# TrusskeyV2.net
KiCad netlist of a schematic drawn in EAGLE
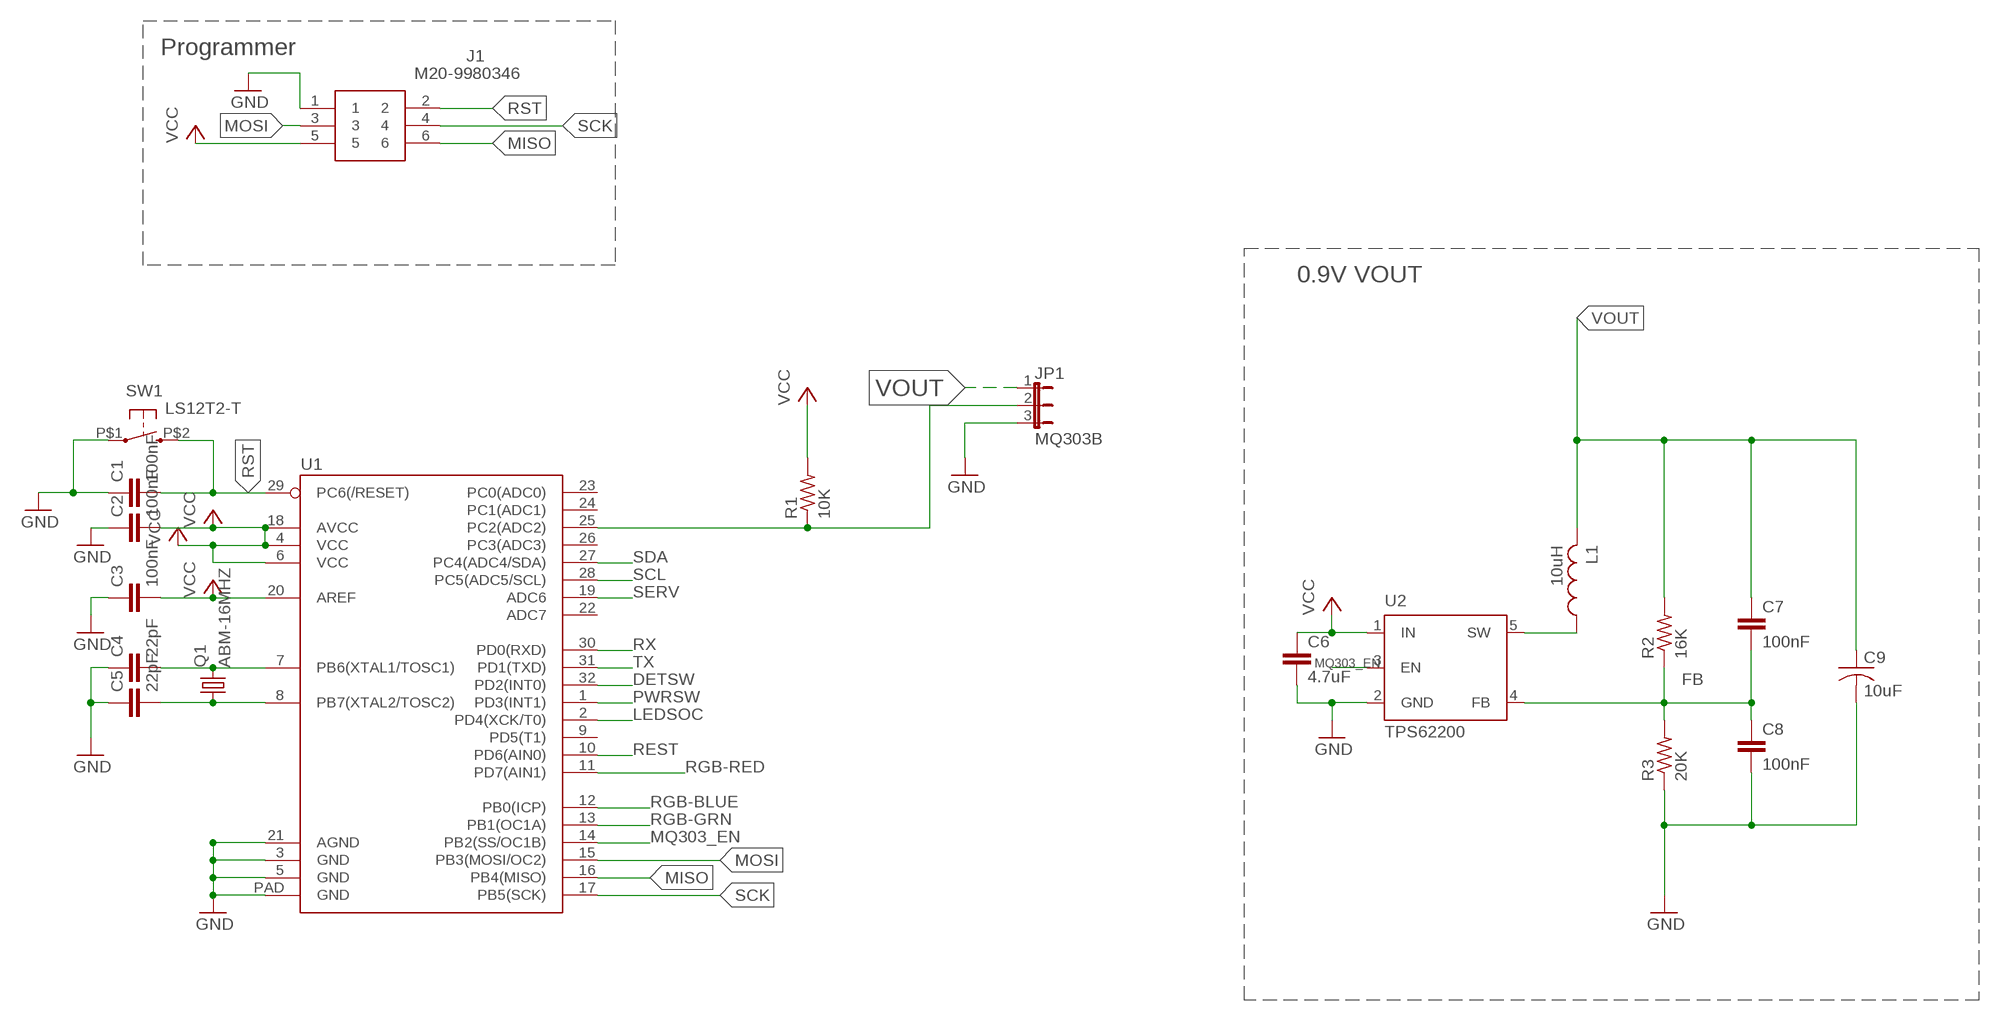
[diagram p0: schematic, sheet 1]
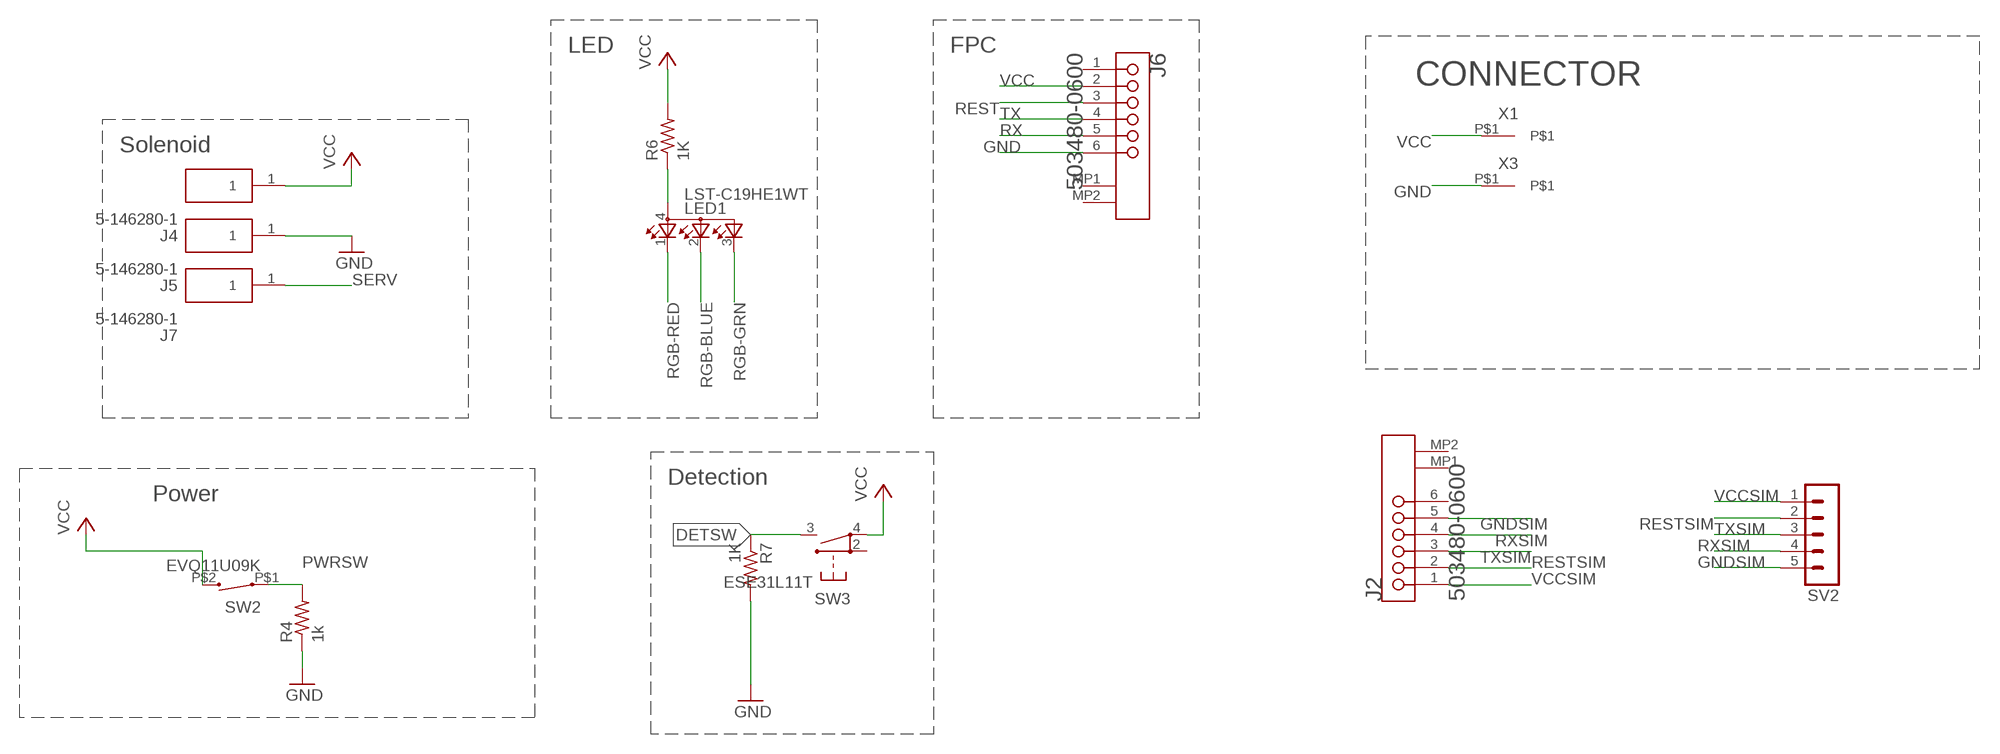
[diagram p1: schematic, sheet 2]
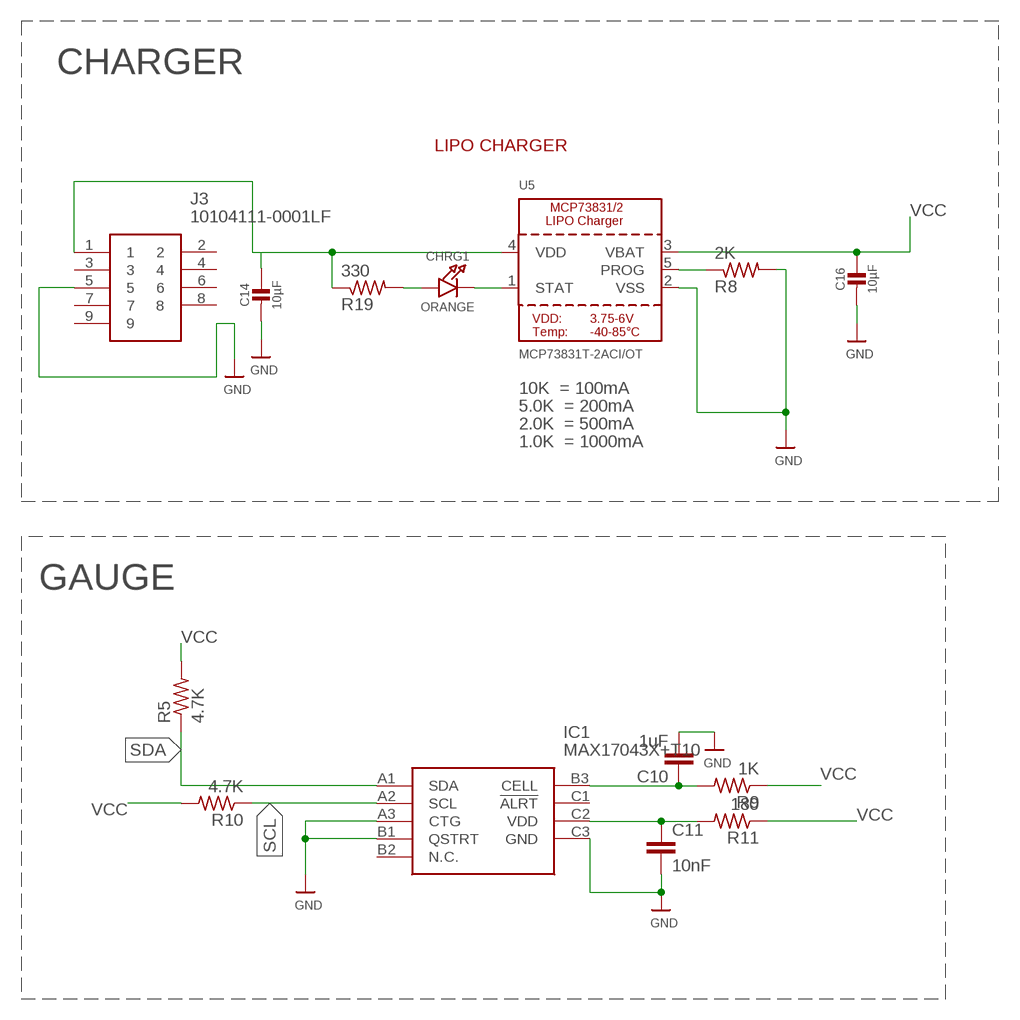
[diagram p2: schematic, sheet 3]

(export (version "E")
  (design (tool "Eeschema 10.0.6"))
  (components
    (comp (ref "J2")
      (value "MOLEX_503480-0600MOLEX_503480-0600_0_0")
      (footprint "eagle-import:MOLEX_503480-0600_0")
      (fields (field (name "MF") "Molex") (field (name "MPN") "503480-0600"))
      (libsource (lib "eagle-import") (part "MOLEX_503480-0600MOLEX_503480-0600_0_0"))
    )
    (comp (ref "J4")
      (value "5-146280-1")
      (footprint "eagle-import:HDRV1W67P0X254_1X1_213X234X821")
      (fields (field (name "MOUSER_PART_NUMBER") "571-51462801"))
      (libsource (lib "eagle-import") (part "5-146280-1"))
    )
    (comp (ref "J5")
      (value "5-146280-1")
      (footprint "eagle-import:HDRV1W67P0X254_1X1_213X234X821")
      (fields (field (name "MOUSER_PART_NUMBER") "571-51462801"))
      (libsource (lib "eagle-import") (part "5-146280-1"))
    )
    (comp (ref "J6")
      (value "MOLEX_503480-0600MOLEX_503480-0600_0_0")
      (footprint "eagle-import:MOLEX_503480-0600_0")
      (fields (field (name "MF") "Molex") (field (name "MPN") "503480-0600"))
      (libsource (lib "eagle-import") (part "MOLEX_503480-0600MOLEX_503480-0600_0_0"))
    )
    (comp (ref "J7")
      (value "5-146280-1")
      (footprint "eagle-import:HDRV1W67P0X254_1X1_213X234X821")
      (fields (field (name "MOUSER_PART_NUMBER") "571-51462801"))
      (libsource (lib "eagle-import") (part "5-146280-1"))
    )
    (comp (ref "LED1")
      (value "LST-C19HE1WT")
      (footprint "eagle-import:LST-C19HE1WT")
      (libsource (lib "eagle-import") (part "LST-C19HE1WT"))
    )
    (comp (ref "R4")
      (value "1k")
      (footprint "eagle-import:R0402")
      (libsource (lib "eagle-import") (part "R-US_R0402"))
    )
    (comp (ref "R6")
      (value "1K")
      (footprint "eagle-import:R0402")
      (libsource (lib "eagle-import") (part "R-US_R0402"))
    )
    (comp (ref "R7")
      (value "1K")
      (footprint "eagle-import:R0402")
      (libsource (lib "eagle-import") (part "R-US_R0402"))
    )
    (comp (ref "SV2")
      (value "MA05-1")
      (footprint "eagle-import:MA05-1")
      (libsource (lib "eagle-import") (part "MA05-1"))
    )
    (comp (ref "SW2")
      (value "EVQ11U09K")
      (footprint "eagle-import:EVQ11U-09K")
      (libsource (lib "eagle-import") (part "EVQ11U09K"))
    )
    (comp (ref "SW3")
      (value "ESE31L11T")
      (footprint "eagle-import:SWITCH")
      (libsource (lib "eagle-import") (part "ESE31L11T"))
    )
    (comp (ref "X1")
      (value "CON-1PIN")
      (footprint "eagle-import:CON-1PIN")
      (libsource (lib "eagle-import") (part "CON-1PIN"))
    )
    (comp (ref "X3")
      (value "CON-1PIN")
      (footprint "eagle-import:CON-1PIN")
      (libsource (lib "eagle-import") (part "CON-1PIN"))
    )
    (comp (ref "C1")
      (value "100nF")
      (footprint "eagle-import:C0603")
      (libsource (lib "eagle-import") (part "C-EUC0603"))
    )
    (comp (ref "C2")
      (value "100nF")
      (footprint "eagle-import:C0603")
      (libsource (lib "eagle-import") (part "C-EUC0603"))
    )
    (comp (ref "C3")
      (value "100nF")
      (footprint "eagle-import:C0603")
      (libsource (lib "eagle-import") (part "C-EUC0603"))
    )
    (comp (ref "C4")
      (value "22pF")
      (footprint "eagle-import:C0603")
      (libsource (lib "eagle-import") (part "C-EUC0603"))
    )
    (comp (ref "C5")
      (value "22pF")
      (footprint "eagle-import:C0603")
      (libsource (lib "eagle-import") (part "C-EUC0603"))
    )
    (comp (ref "C6")
      (value "4.7uF")
      (footprint "eagle-import:C0402")
      (libsource (lib "eagle-import") (part "C-EUC0402"))
    )
    (comp (ref "C7")
      (value "100nF")
      (footprint "eagle-import:C0402")
      (libsource (lib "eagle-import") (part "C-EUC0402"))
    )
    (comp (ref "C8")
      (value "100nF")
      (footprint "eagle-import:C0402")
      (libsource (lib "eagle-import") (part "C-EUC0402"))
    )
    (comp (ref "C9")
      (value "10uF")
      (footprint "eagle-import:C0805K")
      (libsource (lib "eagle-import") (part "C-USC0805K"))
    )
    (comp (ref "J1")
      (value "M20-9980346")
      (footprint "eagle-import:HDRV6W64P254_2X3_762X508X868P")
      (fields (field (name "MOUSER_PART_NUMBER") "855-M20-9980346"))
      (libsource (lib "eagle-import") (part "M20-9980346"))
    )
    (comp (ref "JP1")
      (value "MQ303B")
      (footprint "eagle-import:JP2")
      (libsource (lib "eagle-import") (part "JP2E"))
    )
    (comp (ref "L1")
      (value "10uH")
      (footprint "eagle-import:L2825P")
      (libsource (lib "eagle-import") (part "L-USL2825P"))
    )
    (comp (ref "Q1")
      (value "ABM-16MHZ")
      (footprint "eagle-import:ABM-16MHZ")
      (libsource (lib "eagle-import") (part "ABM-16MHZ"))
    )
    (comp (ref "R1")
      (value "10K")
      (footprint "eagle-import:R0402")
      (libsource (lib "eagle-import") (part "R-US_R0402"))
    )
    (comp (ref "R2")
      (value "16K")
      (footprint "eagle-import:R0402")
      (libsource (lib "eagle-import") (part "R-US_R0402"))
    )
    (comp (ref "R3")
      (value "20K")
      (footprint "eagle-import:R0402")
      (libsource (lib "eagle-import") (part "R-US_R0402"))
    )
    (comp (ref "SW1")
      (value "LS12T2-T")
      (footprint "eagle-import:LS12T2-T")
      (libsource (lib "eagle-import") (part "LS12T2-T"))
    )
    (comp (ref "U1")
      (value "ATMEGA328P_MLFMLF32")
      (footprint "eagle-import:MLF32-PAD")
      (libsource (lib "eagle-import") (part "ATMEGA328P_MLFMLF32"))
    )
    (comp (ref "U2")
      (value "TPS62200")
      (footprint "eagle-import:TPS62200")
      (libsource (lib "eagle-import") (part "TPS62200"))
    )
    (comp (ref "C10")
      (value "1uF")
      (footprint "eagle-import:C0603")
      (libsource (lib "eagle-import") (part "C-EUC0603"))
    )
    (comp (ref "C11")
      (value "10nF")
      (footprint "eagle-import:C0603")
      (libsource (lib "eagle-import") (part "C-EUC0603"))
    )
    (comp (ref "C14")
      (value "10µF")
      (footprint "eagle-import:0805-NO")
      (libsource (lib "eagle-import") (part "CAP_CERAMIC0805-NOOUTLINE"))
    )
    (comp (ref "C16")
      (value "10µF")
      (footprint "eagle-import:0805-NO")
      (libsource (lib "eagle-import") (part "CAP_CERAMIC0805-NOOUTLINE"))
    )
    (comp (ref "CHRG1")
      (value "ORANGE")
      (footprint "eagle-import:CHIPLED_0805_NOOUTLINE")
      (libsource (lib "eagle-import") (part "LED0805_NOOUTLINE"))
    )
    (comp (ref "IC1")
      (value "MAX17043X+T10")
      (footprint "eagle-import:BGA9C40P3X3_160X142X69")
      (fields (field (name "MOUSER_PART_NUMBER") "700-MAX17043X+T10"))
      (libsource (lib "eagle-import") (part "MAX17043X+T10"))
    )
    (comp (ref "J3")
      (value "10104111-0001LF")
      (footprint "eagle-import:101041110001LF")
      (fields (field (name "MOUSER_PART_NUMBER") "649-10104111-0001LF"))
      (libsource (lib "eagle-import") (part "10104111-0001LF"))
    )
    (comp (ref "R5")
      (value "4.7K")
      (footprint "eagle-import:R0402")
      (libsource (lib "eagle-import") (part "R-US_R0402"))
    )
    (comp (ref "R8")
      (value "2K")
      (footprint "eagle-import:R0402")
      (libsource (lib "eagle-import") (part "R-US_R0402"))
    )
    (comp (ref "R9")
      (value "1K")
      (footprint "eagle-import:R0402")
      (libsource (lib "eagle-import") (part "R-US_R0402"))
    )
    (comp (ref "R10")
      (value "4.7K")
      (footprint "eagle-import:R0402")
      (libsource (lib "eagle-import") (part "R-US_R0402"))
    )
    (comp (ref "R11")
      (value "180")
      (footprint "eagle-import:R0402")
      (libsource (lib "eagle-import") (part "R-US_R0402"))
    )
    (comp (ref "R19")
      (value "330")
      (footprint "eagle-import:R0402")
      (libsource (lib "eagle-import") (part "R-US_R0402"))
    )
    (comp (ref "U5")
      (value "MCP73831T-2ACI/OT")
      (footprint "eagle-import:SOT23-5")
      (libsource (lib "eagle-import") (part "MCP73831/2"))
    )
  )
  (nets
    (net (code "1") (name "DETSW") (class "Default")
      (node (ref "R7") (pin "1") (pinfunction "1_1") (pintype "passive"))
      (node (ref "SW3") (pin "3") (pinfunction "1_3") (pintype "passive"))
      (node (ref "U1") (pin "32") (pinfunction "PD2(INT0)_32") (pintype "bidirectional"))
    )
    (net (code "2") (name "FB") (class "Default")
      (node (ref "C7") (pin "2") (pinfunction "2_2") (pintype "passive"))
      (node (ref "C8") (pin "1") (pinfunction "1_1") (pintype "passive"))
      (node (ref "R2") (pin "1") (pinfunction "1_1") (pintype "passive"))
      (node (ref "R3") (pin "2") (pinfunction "2_2") (pintype "passive"))
      (node (ref "U2") (pin "4") (pinfunction "FB_4") (pintype "passive"))
    )
    (net (code "3") (name "GND") (class "Default")
      (node (ref "C1") (pin "1") (pinfunction "1_1") (pintype "passive"))
      (node (ref "C10") (pin "2") (pinfunction "2_2") (pintype "passive"))
      (node (ref "C11") (pin "2") (pinfunction "2_2") (pintype "passive"))
      (node (ref "C14") (pin "2") (pinfunction "2_2") (pintype "passive"))
      (node (ref "C16") (pin "2") (pinfunction "2_2") (pintype "passive"))
      (node (ref "C2") (pin "1") (pinfunction "1_1") (pintype "passive"))
      (node (ref "C3") (pin "1") (pinfunction "1_1") (pintype "passive"))
      (node (ref "C4") (pin "1") (pinfunction "1_1") (pintype "passive"))
      (node (ref "C5") (pin "1") (pinfunction "1_1") (pintype "passive"))
      (node (ref "C6") (pin "2") (pinfunction "2_2") (pintype "passive"))
      (node (ref "C8") (pin "2") (pinfunction "2_2") (pintype "passive"))
      (node (ref "C9") (pin "2") (pinfunction "2_2") (pintype "passive"))
      (node (ref "IC1") (pin "A3") (pinfunction "CTG_A3") (pintype "bidirectional"))
      (node (ref "IC1") (pin "B1") (pinfunction "QSTRT_B1") (pintype "bidirectional"))
      (node (ref "IC1") (pin "C3") (pinfunction "GND_C3") (pintype "bidirectional"))
      (node (ref "J1") (pin "1") (pinfunction "1_1") (pintype "bidirectional"))
      (node (ref "J3") (pin "5") (pinfunction "5_5") (pintype "bidirectional"))
      (node (ref "J5") (pin "1") (pinfunction "1_1") (pintype "bidirectional"))
      (node (ref "J6") (pin "6") (pinfunction "6_6") (pintype "passive"))
      (node (ref "JP1") (pin "3") (pinfunction "3_3") (pintype "passive"))
      (node (ref "R3") (pin "1") (pinfunction "1_1") (pintype "passive"))
      (node (ref "R4") (pin "1") (pinfunction "1_1") (pintype "passive"))
      (node (ref "R7") (pin "2") (pinfunction "2_2") (pintype "passive"))
      (node (ref "R8") (pin "2") (pinfunction "2_2") (pintype "passive"))
      (node (ref "SW1") (pin "P$1") (pinfunction "S1_P$1") (pintype "passive"))
      (node (ref "U1") (pin "21") (pinfunction "AGND_21") (pintype "bidirectional"))
      (node (ref "U1") (pin "3") (pinfunction "GND_3") (pintype "bidirectional"))
      (node (ref "U1") (pin "5") (pinfunction "GND_5") (pintype "bidirectional"))
      (node (ref "U1") (pin "PAD") (pinfunction "GND_PAD") (pintype "bidirectional"))
      (node (ref "U2") (pin "2") (pinfunction "GND_2") (pintype "power_in"))
      (node (ref "U5") (pin "2") (pinfunction "VSS_2") (pintype "power_in"))
      (node (ref "X3") (pin "P$1") (pinfunction "P$1_P$1") (pintype "bidirectional"))
    )
    (net (code "4") (name "GNDSIM") (class "Default")
      (node (ref "J2") (pin "5") (pinfunction "5_5") (pintype "passive"))
      (node (ref "SV2") (pin "5") (pinfunction "5_5") (pintype "passive"))
    )
    (net (code "5") (name "LEDSOC") (class "Default")
      (node (ref "U1") (pin "2") (pinfunction "PD4(XCK/T0)_2") (pintype "bidirectional"))
    )
    (net (code "6") (name "MISO") (class "Default")
      (node (ref "J1") (pin "6") (pinfunction "6_6") (pintype "bidirectional"))
      (node (ref "U1") (pin "16") (pinfunction "PB4(MISO)_16") (pintype "bidirectional"))
    )
    (net (code "7") (name "MOSI") (class "Default")
      (node (ref "J1") (pin "3") (pinfunction "3_3") (pintype "bidirectional"))
      (node (ref "U1") (pin "15") (pinfunction "PB3(MOSI/OC2)_15") (pintype "bidirectional"))
    )
    (net (code "8") (name "MQ303_EN") (class "Default")
      (node (ref "U1") (pin "14") (pinfunction "PB2(SS/OC1B)_14") (pintype "bidirectional"))
      (node (ref "U2") (pin "3") (pinfunction "EN_3") (pintype "input"))
    )
    (net (code "9") (name "Net-(CHRG1-PadA)") (class "Default")
      (node (ref "CHRG1") (pin "A") (pinfunction "A_A") (pintype "passive"))
      (node (ref "R19") (pin "2") (pinfunction "2_2") (pintype "passive"))
    )
    (net (code "10") (name "Net-(IC1-CELL)") (class "Default")
      (node (ref "C10") (pin "1") (pinfunction "1_1") (pintype "passive"))
      (node (ref "IC1") (pin "B3") (pinfunction "CELL_B3") (pintype "bidirectional"))
      (node (ref "R9") (pin "2") (pinfunction "2_2") (pintype "passive"))
    )
    (net (code "11") (name "Net-(IC1-VDD)") (class "Default")
      (node (ref "C11") (pin "1") (pinfunction "1_1") (pintype "passive"))
      (node (ref "IC1") (pin "C2") (pinfunction "VDD_C2") (pintype "bidirectional"))
      (node (ref "R11") (pin "2") (pinfunction "2_2") (pintype "passive"))
    )
    (net (code "12") (name "Net-(LED1-A)") (class "Default")
      (node (ref "LED1") (pin "4") (pinfunction "A_4") (pintype "passive"))
      (node (ref "R6") (pin "1") (pinfunction "1_1") (pintype "passive"))
    )
    (net (code "13") (name "Net-(Q1-1)") (class "Default")
      (node (ref "C5") (pin "2") (pinfunction "2_2") (pintype "passive"))
      (node (ref "Q1") (pin "P$1") (pinfunction "1_P$1") (pintype "passive"))
      (node (ref "U1") (pin "8") (pinfunction "PB7(XTAL2/TOSC2)_8") (pintype "bidirectional"))
    )
    (net (code "14") (name "Net-(Q1-2)") (class "Default")
      (node (ref "C4") (pin "2") (pinfunction "2_2") (pintype "passive"))
      (node (ref "Q1") (pin "P$2") (pinfunction "2_P$2") (pintype "passive"))
      (node (ref "U1") (pin "7") (pinfunction "PB6(XTAL1/TOSC1)_7") (pintype "bidirectional"))
    )
    (net (code "15") (name "Net-(U1-PC2(ADC2))") (class "Default")
      (node (ref "JP1") (pin "2") (pinfunction "2_2") (pintype "passive"))
      (node (ref "R1") (pin "1") (pinfunction "1_1") (pintype "passive"))
      (node (ref "U1") (pin "25") (pinfunction "PC2(ADC2)_25") (pintype "bidirectional"))
    )
    (net (code "16") (name "Net-(U2-SW)") (class "Default")
      (node (ref "L1") (pin "1") (pinfunction "1_1") (pintype "passive"))
      (node (ref "U2") (pin "5") (pinfunction "SW_5") (pintype "passive"))
    )
    (net (code "17") (name "Net-(U5-PROG)") (class "Default")
      (node (ref "R8") (pin "1") (pinfunction "1_1") (pintype "passive"))
      (node (ref "U5") (pin "5") (pinfunction "PROG_5") (pintype "input"))
    )
    (net (code "18") (name "Net-(U5-STAT)") (class "Default")
      (node (ref "CHRG1") (pin "C") (pinfunction "C_C") (pintype "passive"))
      (node (ref "U5") (pin "1") (pinfunction "STAT_1") (pintype "output"))
    )
    (net (code "19") (name "Net-(U5-VDD)") (class "Default")
      (node (ref "C14") (pin "1") (pinfunction "1_1") (pintype "passive"))
      (node (ref "J3") (pin "1") (pinfunction "1_1") (pintype "bidirectional"))
      (node (ref "R19") (pin "1") (pinfunction "1_1") (pintype "passive"))
      (node (ref "U5") (pin "4") (pinfunction "VDD_4") (pintype "power_in"))
    )
    (net (code "20") (name "PWRSW") (class "Default")
      (node (ref "R4") (pin "2") (pinfunction "2_2") (pintype "passive"))
      (node (ref "SW2") (pin "P$1") (pinfunction "1_P$1") (pintype "passive"))
      (node (ref "U1") (pin "1") (pinfunction "PD3(INT1)_1") (pintype "bidirectional"))
    )
    (net (code "21") (name "REST") (class "Default")
      (node (ref "J6") (pin "3") (pinfunction "3_3") (pintype "passive"))
      (node (ref "U1") (pin "10") (pinfunction "PD6(AIN0)_10") (pintype "bidirectional"))
    )
    (net (code "22") (name "RESTSIM") (class "Default")
      (node (ref "J2") (pin "2") (pinfunction "2_2") (pintype "passive"))
      (node (ref "SV2") (pin "2") (pinfunction "2_2") (pintype "passive"))
    )
    (net (code "23") (name "RGB-BLUE") (class "Default")
      (node (ref "LED1") (pin "2") (pinfunction "CGREEN_2") (pintype "passive"))
      (node (ref "U1") (pin "12") (pinfunction "PB0(ICP)_12") (pintype "bidirectional"))
    )
    (net (code "24") (name "RGB-GRN") (class "Default")
      (node (ref "LED1") (pin "3") (pinfunction "CBLUE_3") (pintype "passive"))
      (node (ref "U1") (pin "13") (pinfunction "PB1(OC1A)_13") (pintype "bidirectional"))
    )
    (net (code "25") (name "RGB-RED") (class "Default")
      (node (ref "LED1") (pin "1") (pinfunction "CRED_1") (pintype "passive"))
      (node (ref "U1") (pin "11") (pinfunction "PD7(AIN1)_11") (pintype "bidirectional"))
    )
    (net (code "26") (name "RST") (class "Default")
      (node (ref "C1") (pin "2") (pinfunction "2_2") (pintype "passive"))
      (node (ref "J1") (pin "2") (pinfunction "2_2") (pintype "bidirectional"))
      (node (ref "SW1") (pin "P$2") (pinfunction "S2_P$2") (pintype "passive"))
      (node (ref "U1") (pin "29") (pinfunction "PC6(/RESET)_29") (pintype "bidirectional"))
    )
    (net (code "27") (name "RX") (class "Default")
      (node (ref "J6") (pin "5") (pinfunction "5_5") (pintype "passive"))
      (node (ref "U1") (pin "30") (pinfunction "PD0(RXD)_30") (pintype "bidirectional"))
    )
    (net (code "28") (name "RXSIM") (class "Default")
      (node (ref "J2") (pin "4") (pinfunction "4_4") (pintype "passive"))
      (node (ref "SV2") (pin "4") (pinfunction "4_4") (pintype "passive"))
    )
    (net (code "29") (name "SCK") (class "Default")
      (node (ref "J1") (pin "4") (pinfunction "4_4") (pintype "bidirectional"))
      (node (ref "U1") (pin "17") (pinfunction "PB5(SCK)_17") (pintype "bidirectional"))
    )
    (net (code "30") (name "SCL") (class "Default")
      (node (ref "IC1") (pin "A2") (pinfunction "SCL_A2") (pintype "bidirectional"))
      (node (ref "R10") (pin "1") (pinfunction "1_1") (pintype "passive"))
      (node (ref "U1") (pin "28") (pinfunction "PC5(ADC5/SCL)_28") (pintype "bidirectional"))
    )
    (net (code "31") (name "SDA") (class "Default")
      (node (ref "IC1") (pin "A1") (pinfunction "SDA_A1") (pintype "bidirectional"))
      (node (ref "R5") (pin "1") (pinfunction "1_1") (pintype "passive"))
      (node (ref "U1") (pin "27") (pinfunction "PC4(ADC4/SDA)_27") (pintype "bidirectional"))
    )
    (net (code "32") (name "SERV") (class "Default")
      (node (ref "J7") (pin "1") (pinfunction "1_1") (pintype "bidirectional"))
      (node (ref "U1") (pin "19") (pinfunction "ADC6_19") (pintype "bidirectional"))
    )
    (net (code "33") (name "TX") (class "Default")
      (node (ref "J6") (pin "4") (pinfunction "4_4") (pintype "passive"))
      (node (ref "U1") (pin "31") (pinfunction "PD1(TXD)_31") (pintype "bidirectional"))
    )
    (net (code "34") (name "TXSIM") (class "Default")
      (node (ref "J2") (pin "3") (pinfunction "3_3") (pintype "passive"))
      (node (ref "SV2") (pin "3") (pinfunction "3_3") (pintype "passive"))
    )
    (net (code "35") (name "VCC") (class "Default")
      (node (ref "C16") (pin "1") (pinfunction "1_1") (pintype "passive"))
      (node (ref "C2") (pin "2") (pinfunction "2_2") (pintype "passive"))
      (node (ref "C3") (pin "2") (pinfunction "2_2") (pintype "passive"))
      (node (ref "C6") (pin "1") (pinfunction "1_1") (pintype "passive"))
      (node (ref "J1") (pin "5") (pinfunction "5_5") (pintype "bidirectional"))
      (node (ref "J4") (pin "1") (pinfunction "1_1") (pintype "bidirectional"))
      (node (ref "J6") (pin "2") (pinfunction "2_2") (pintype "passive"))
      (node (ref "R1") (pin "2") (pinfunction "2_2") (pintype "passive"))
      (node (ref "R10") (pin "2") (pinfunction "2_2") (pintype "passive"))
      (node (ref "R11") (pin "1") (pinfunction "1_1") (pintype "passive"))
      (node (ref "R5") (pin "2") (pinfunction "2_2") (pintype "passive"))
      (node (ref "R6") (pin "2") (pinfunction "2_2") (pintype "passive"))
      (node (ref "R9") (pin "1") (pinfunction "1_1") (pintype "passive"))
      (node (ref "SW2") (pin "P$2") (pinfunction "2_P$2") (pintype "passive"))
      (node (ref "SW3") (pin "4") (pinfunction "C3_4") (pintype "passive"))
      (node (ref "U1") (pin "18") (pinfunction "AVCC_18") (pintype "bidirectional"))
      (node (ref "U1") (pin "20") (pinfunction "AREF_20") (pintype "bidirectional"))
      (node (ref "U1") (pin "4") (pinfunction "VCC_4") (pintype "bidirectional"))
      (node (ref "U1") (pin "6") (pinfunction "VCC_6") (pintype "bidirectional"))
      (node (ref "U2") (pin "1") (pinfunction "IN_1") (pintype "input"))
      (node (ref "U5") (pin "3") (pinfunction "VBAT_3") (pintype "power_in"))
      (node (ref "X1") (pin "P$1") (pinfunction "P$1_P$1") (pintype "bidirectional"))
    )
    (net (code "36") (name "VCCSIM") (class "Default")
      (node (ref "J2") (pin "1") (pinfunction "1_1") (pintype "passive"))
      (node (ref "SV2") (pin "1") (pinfunction "1_1") (pintype "passive"))
    )
    (net (code "37") (name "VOUT") (class "Default")
      (node (ref "C7") (pin "1") (pinfunction "1_1") (pintype "passive"))
      (node (ref "C9") (pin "1") (pinfunction "1_1") (pintype "passive"))
      (node (ref "JP1") (pin "1") (pinfunction "1_1") (pintype "passive"))
      (node (ref "L1") (pin "2") (pinfunction "2_2") (pintype "passive"))
      (node (ref "R2") (pin "2") (pinfunction "2_2") (pintype "passive"))
    )
    (net (code "38") (name "unconnected-(IC1-N.C.-PadB2)") (class "Default")
      (node (ref "IC1") (pin "B2") (pinfunction "N.C._B2") (pintype "no_connect"))
    )
    (net (code "39") (name "unconnected-(IC1-~{ALRT}-PadC1)") (class "Default")
      (node (ref "IC1") (pin "C1") (pinfunction "~{ALRT}_C1") (pintype "bidirectional"))
    )
    (net (code "40") (name "unconnected-(J2-Pad6)") (class "Default")
      (node (ref "J2") (pin "6") (pinfunction "6_6") (pintype "passive"))
    )
    (net (code "41") (name "unconnected-(J2-PadMP1)") (class "Default")
      (node (ref "J2") (pin "MP1") (pinfunction "MP1_MP1") (pintype "passive"))
    )
    (net (code "42") (name "unconnected-(J2-PadMP2)") (class "Default")
      (node (ref "J2") (pin "MP2") (pinfunction "MP2_MP2") (pintype "passive"))
    )
    (net (code "43") (name "unconnected-(J3-Pad2)") (class "Default")
      (node (ref "J3") (pin "2") (pinfunction "2_2") (pintype "bidirectional"))
    )
    (net (code "44") (name "unconnected-(J3-Pad3)") (class "Default")
      (node (ref "J3") (pin "3") (pinfunction "3_3") (pintype "bidirectional"))
    )
    (net (code "45") (name "unconnected-(J3-Pad4)") (class "Default")
      (node (ref "J3") (pin "4") (pinfunction "4_4") (pintype "bidirectional"))
    )
    (net (code "46") (name "unconnected-(J3-Pad6)") (class "Default")
      (node (ref "J3") (pin "6") (pinfunction "6_6") (pintype "bidirectional"))
    )
    (net (code "47") (name "unconnected-(J3-Pad7)") (class "Default")
      (node (ref "J3") (pin "7") (pinfunction "7_7") (pintype "bidirectional"))
    )
    (net (code "48") (name "unconnected-(J3-Pad8)") (class "Default")
      (node (ref "J3") (pin "8") (pinfunction "8_8") (pintype "bidirectional"))
    )
    (net (code "49") (name "unconnected-(J3-Pad9)") (class "Default")
      (node (ref "J3") (pin "9") (pinfunction "9_9") (pintype "bidirectional"))
    )
    (net (code "50") (name "unconnected-(J6-Pad1)") (class "Default")
      (node (ref "J6") (pin "1") (pinfunction "1_1") (pintype "passive"))
    )
    (net (code "51") (name "unconnected-(J6-PadMP1)") (class "Default")
      (node (ref "J6") (pin "MP1") (pinfunction "MP1_MP1") (pintype "passive"))
    )
    (net (code "52") (name "unconnected-(J6-PadMP2)") (class "Default")
      (node (ref "J6") (pin "MP2") (pinfunction "MP2_MP2") (pintype "passive"))
    )
    (net (code "53") (name "unconnected-(SW3-C2-Pad2)") (class "Default")
      (node (ref "SW3") (pin "2") (pinfunction "C2_2") (pintype "passive"))
    )
    (net (code "54") (name "unconnected-(U1-ADC7-Pad22)") (class "Default")
      (node (ref "U1") (pin "22") (pinfunction "ADC7_22") (pintype "bidirectional"))
    )
    (net (code "55") (name "unconnected-(U1-PC0(ADC0)-Pad23)") (class "Default")
      (node (ref "U1") (pin "23") (pinfunction "PC0(ADC0)_23") (pintype "bidirectional"))
    )
    (net (code "56") (name "unconnected-(U1-PC1(ADC1)-Pad24)") (class "Default")
      (node (ref "U1") (pin "24") (pinfunction "PC1(ADC1)_24") (pintype "bidirectional"))
    )
    (net (code "57") (name "unconnected-(U1-PC3(ADC3)-Pad26)") (class "Default")
      (node (ref "U1") (pin "26") (pinfunction "PC3(ADC3)_26") (pintype "bidirectional"))
    )
    (net (code "58") (name "unconnected-(U1-PD5(T1)-Pad9)") (class "Default")
      (node (ref "U1") (pin "9") (pinfunction "PD5(T1)_9") (pintype "bidirectional"))
    )
  )
)
